# mcuboardschematic.net
KiCad netlist of a schematic drawn in EasyEDA Pro
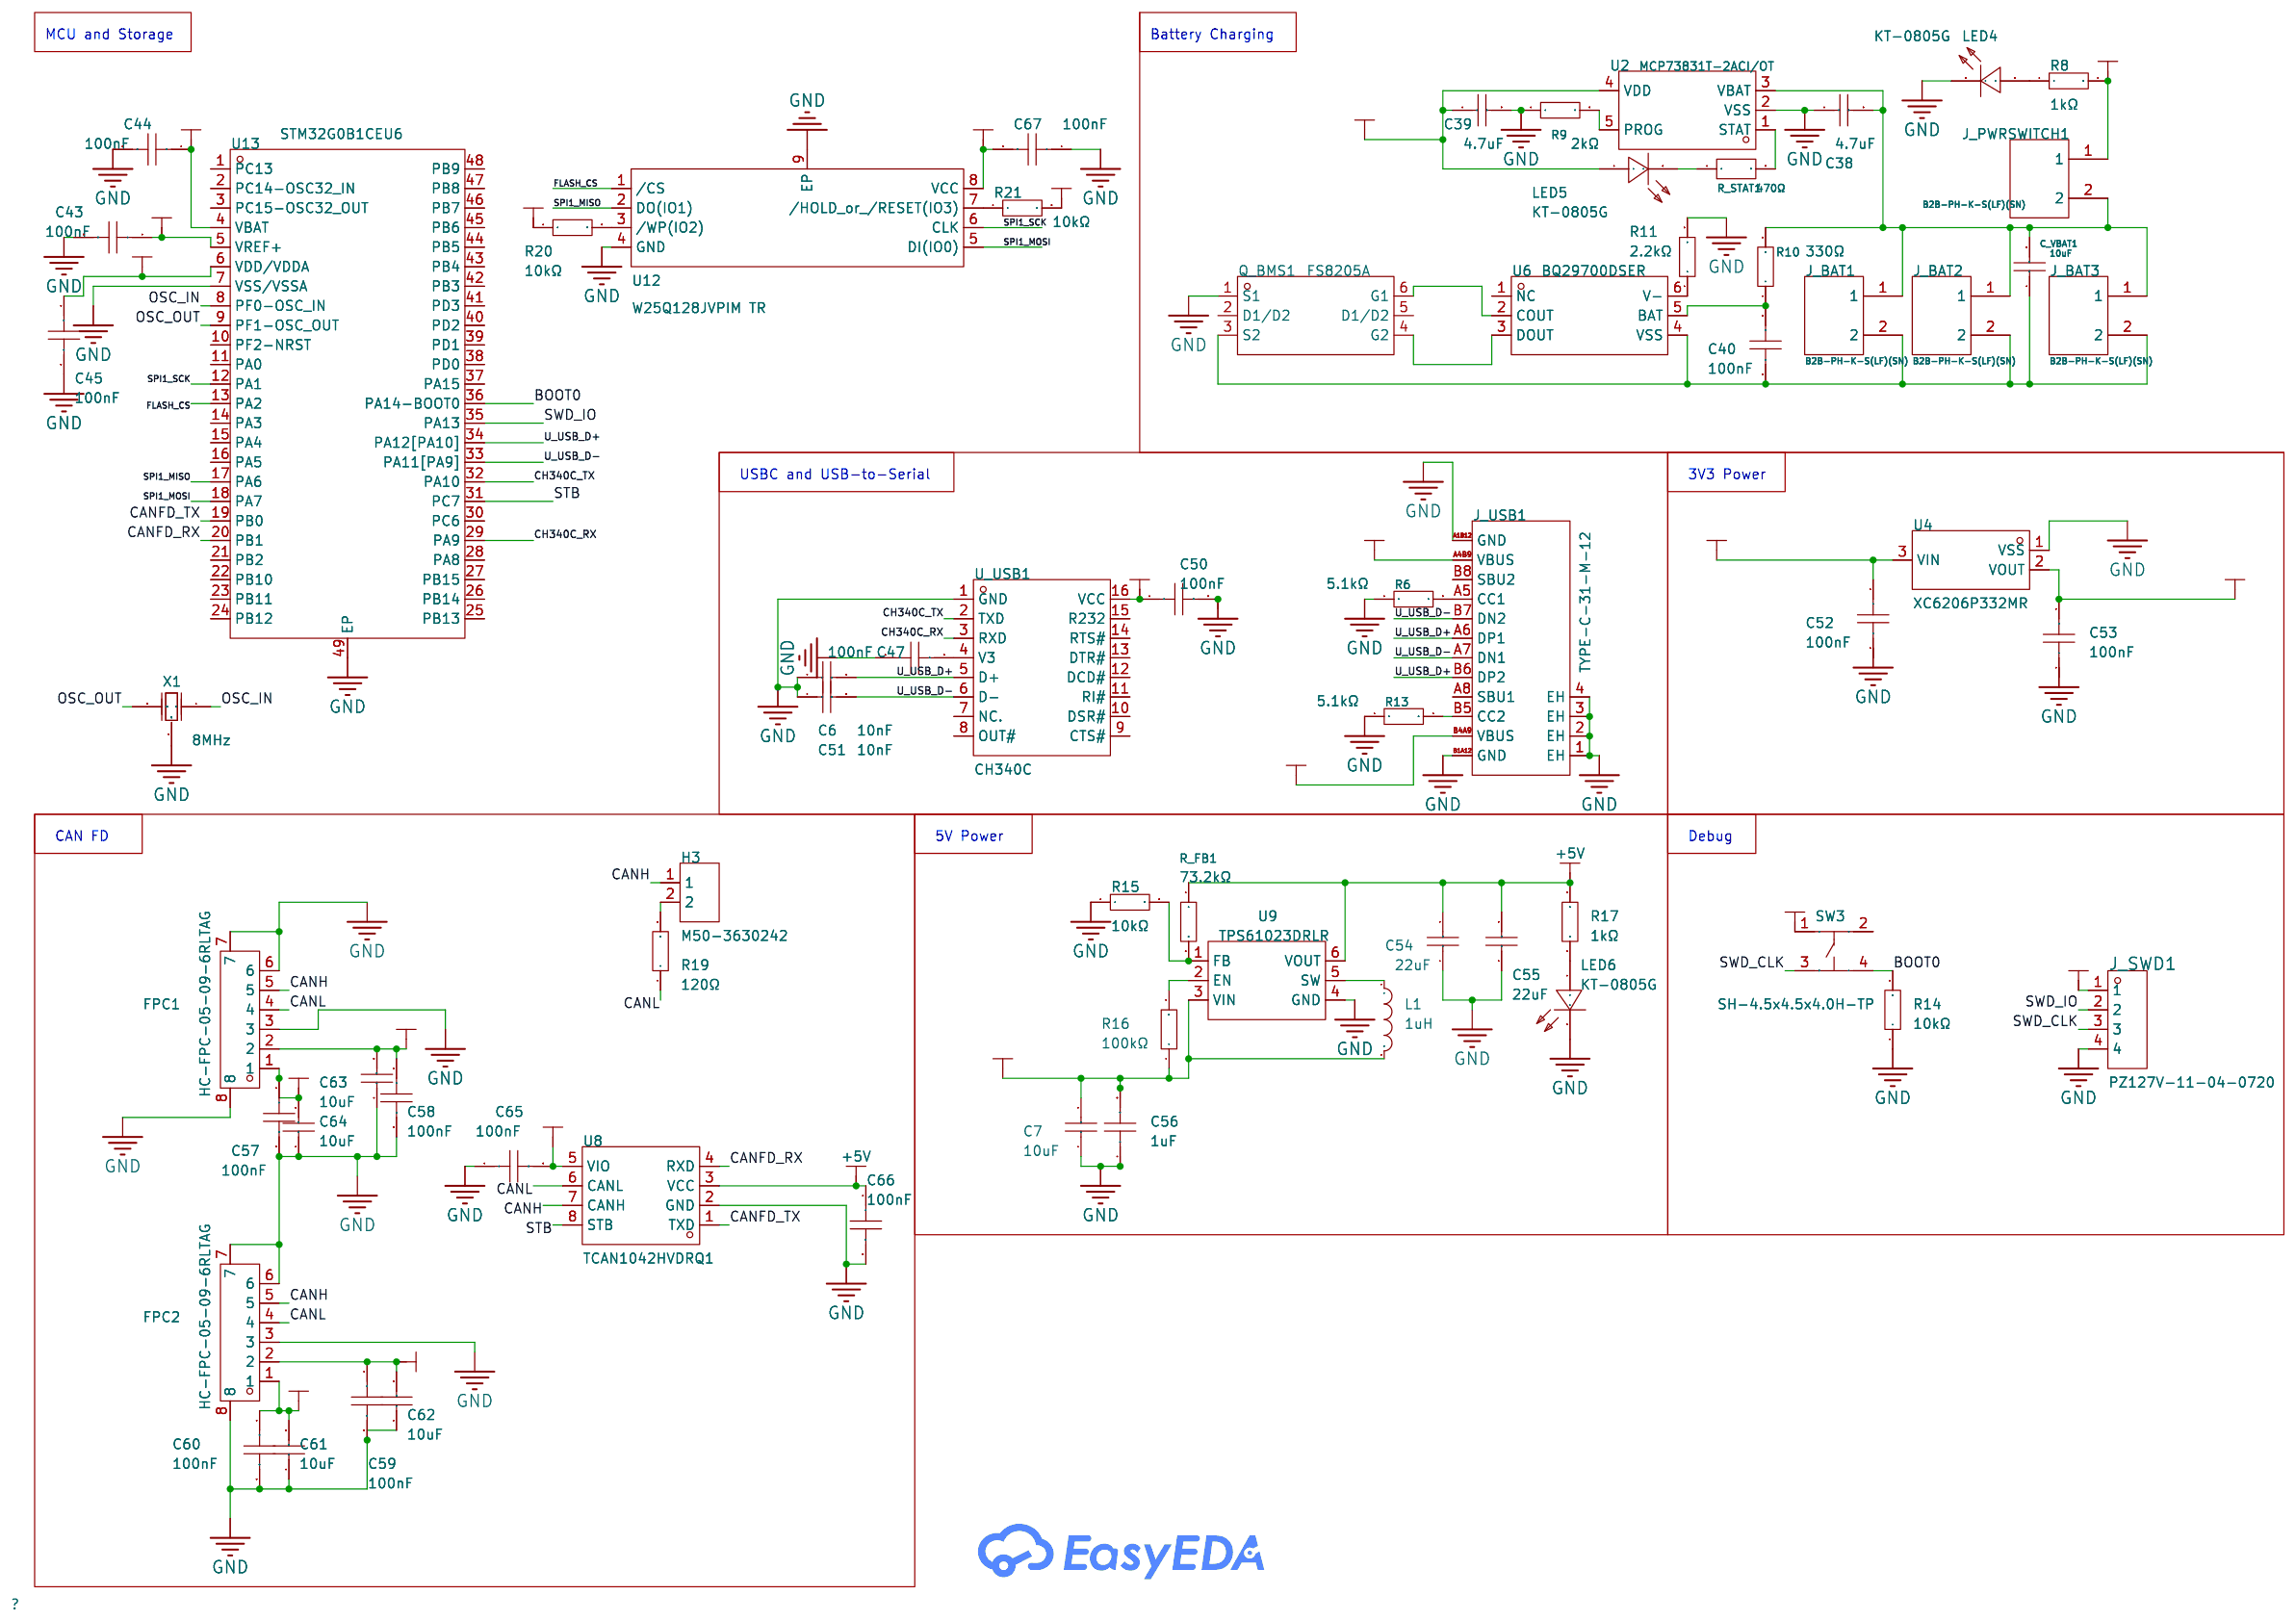
[diagram p0: schematic sheet]

(export (version "E")
  (design (tool "Eeschema 10.0.6"))
  (components
    (comp (ref "C6")
      (value "10nF")
      (footprint "easyedapro:C0402")
      (description "Capacitance:10nF Tolerance:±10% Tolerance:±10% Voltage Rating:50V Temperature Coefficient:X7R")
      (fields
        (field (name "Manufacturer Part") "CL05B103KB5NNNC")
        (field (name "Manufacturer") "SAMSUNG(三星)")
      )
      (libsource (lib "easyedapro") (part "CL05B103KB5NNNC"))
    )
    (comp (ref "C7")
      (value "10uF")
      (footprint "easyedapro:C0402")
      (description "Capacitance:10uF Tolerance:±20% Tolerance:±20% Voltage Rating:6.3V Temperature Coefficient:X5R")
      (fields
        (field (name "Manufacturer Part") "CL05A106MQ5NUNC")
        (field (name "Manufacturer") "SAMSUNG(三星)")
      )
      (libsource (lib "easyedapro") (part "CL05A106MQ5NUNC"))
    )
    (comp (ref "C38")
      (value "4.7uF")
      (footprint "easyedapro:C1206")
      (description "Capacitance:4.7uF Tolerance:±10% Tolerance:±10% Voltage Rating:25V Temperature Coefficient:X7R")
      (fields
        (field (name "Manufacturer Part") "CL31B475KAHNNNE")
        (field (name "Manufacturer") "SAMSUNG(三星)")
      )
      (libsource (lib "easyedapro") (part "CL31B475KAHNNNE"))
    )
    (comp (ref "C39")
      (value "4.7uF")
      (footprint "easyedapro:C1206")
      (description "Capacitance:4.7uF Tolerance:±10% Tolerance:±10% Voltage Rating:25V Temperature Coefficient:X7R")
      (fields
        (field (name "Manufacturer Part") "CL31B475KAHNNNE")
        (field (name "Manufacturer") "SAMSUNG(三星)")
      )
      (libsource (lib "easyedapro") (part "CL31B475KAHNNNE"))
    )
    (comp (ref "C40")
      (value "100nF")
      (footprint "easyedapro:C0402")
      (description "Capacitance:100nF Tolerance:±10% Tolerance:±10% Voltage Rating:16V Temperature Coefficient:X7R")
      (fields
        (field (name "Manufacturer Part") "CL05B104KO5NNNC")
        (field (name "Manufacturer") "SAMSUNG(三星)")
      )
      (libsource (lib "easyedapro") (part "CL05B104KO5NNNC"))
    )
    (comp (ref "C43")
      (value "100nF")
      (footprint "easyedapro:C0402")
      (description "Capacitance:100nF Tolerance:±10% Tolerance:±10% Voltage Rating:16V Temperature Coefficient:X7R")
      (fields
        (field (name "Manufacturer Part") "CL05B104KO5NNNC")
        (field (name "Manufacturer") "SAMSUNG(三星)")
      )
      (libsource (lib "easyedapro") (part "CL05B104KO5NNNC"))
    )
    (comp (ref "C44")
      (value "100nF")
      (footprint "easyedapro:C0402")
      (description "Capacitance:100nF Tolerance:±10% Tolerance:±10% Voltage Rating:16V Temperature Coefficient:X7R")
      (fields
        (field (name "Manufacturer Part") "CL05B104KO5NNNC")
        (field (name "Manufacturer") "SAMSUNG(三星)")
      )
      (libsource (lib "easyedapro") (part "CL05B104KO5NNNC"))
    )
    (comp (ref "C45")
      (value "100nF")
      (footprint "easyedapro:C0402")
      (description "Capacitance:100nF Tolerance:±10% Tolerance:±10% Voltage Rating:16V Temperature Coefficient:X7R")
      (fields
        (field (name "Manufacturer Part") "CL05B104KO5NNNC")
        (field (name "Manufacturer") "SAMSUNG(三星)")
      )
      (libsource (lib "easyedapro") (part "CL05B104KO5NNNC"))
    )
    (comp (ref "C47")
      (value "100nF")
      (footprint "easyedapro:C0402")
      (description "Capacitance:100nF Tolerance:±10% Tolerance:±10% Voltage Rating:16V Temperature Coefficient:X7R")
      (fields
        (field (name "Manufacturer Part") "CL05B104KO5NNNC")
        (field (name "Manufacturer") "SAMSUNG(三星)")
      )
      (libsource (lib "easyedapro") (part "CL05B104KO5NNNC"))
    )
    (comp (ref "C50")
      (value "100nF")
      (footprint "easyedapro:C0402")
      (description "Capacitance:100nF Tolerance:±10% Tolerance:±10% Voltage Rating:16V Temperature Coefficient:X7R")
      (fields
        (field (name "Manufacturer Part") "CL05B104KO5NNNC")
        (field (name "Manufacturer") "SAMSUNG(三星)")
      )
      (libsource (lib "easyedapro") (part "CL05B104KO5NNNC"))
    )
    (comp (ref "C51")
      (value "10nF")
      (footprint "easyedapro:C0402")
      (description "Capacitance:10nF Tolerance:±10% Tolerance:±10% Voltage Rating:50V Temperature Coefficient:X7R")
      (fields
        (field (name "Manufacturer Part") "CL05B103KB5NNNC")
        (field (name "Manufacturer") "SAMSUNG(三星)")
      )
      (libsource (lib "easyedapro") (part "CL05B103KB5NNNC"))
    )
    (comp (ref "C52")
      (value "100nF")
      (footprint "easyedapro:C0402")
      (description "Capacitance:100nF Tolerance:±10% Tolerance:±10% Voltage Rating:16V Temperature Coefficient:X7R")
      (fields
        (field (name "Manufacturer Part") "CL05B104KO5NNNC")
        (field (name "Manufacturer") "SAMSUNG(三星)")
      )
      (libsource (lib "easyedapro") (part "CL05B104KO5NNNC"))
    )
    (comp (ref "C53")
      (value "100nF")
      (footprint "easyedapro:C0402")
      (description "Capacitance:100nF Tolerance:±10% Tolerance:±10% Voltage Rating:16V Temperature Coefficient:X7R")
      (fields
        (field (name "Manufacturer Part") "CL05B104KO5NNNC")
        (field (name "Manufacturer") "SAMSUNG(三星)")
      )
      (libsource (lib "easyedapro") (part "CL05B104KO5NNNC"))
    )
    (comp (ref "C54")
      (value "22uF")
      (footprint "easyedapro:C1206")
      (description "Capacitance:22uF Tolerance:±10% Tolerance:±10% Voltage Rating:25V Temperature Coefficient:X5R")
      (fields
        (field (name "Manufacturer Part") "CL31A226KAHNNNE")
        (field (name "Manufacturer") "SAMSUNG(三星)")
      )
      (libsource (lib "easyedapro") (part "CL31A226KAHNNNE"))
    )
    (comp (ref "C55")
      (value "22uF")
      (footprint "easyedapro:C1206")
      (description "Capacitance:22uF Tolerance:±10% Tolerance:±10% Voltage Rating:25V Temperature Coefficient:X5R")
      (fields
        (field (name "Manufacturer Part") "CL31A226KAHNNNE")
        (field (name "Manufacturer") "SAMSUNG(三星)")
      )
      (libsource (lib "easyedapro") (part "CL31A226KAHNNNE"))
    )
    (comp (ref "C56")
      (value "1uF")
      (footprint "easyedapro:C0402")
      (description "Capacitance:1uF Tolerance:±10% Tolerance:±10% Voltage Rating:25V Temperature Coefficient:X5R")
      (fields
        (field (name "Manufacturer Part") "CL05A105KA5NQNC")
        (field (name "Manufacturer") "SAMSUNG(三星)")
      )
      (libsource (lib "easyedapro") (part "CL05A105KA5NQNC"))
    )
    (comp (ref "C57")
      (value "100nF")
      (footprint "easyedapro:C0402")
      (description "Capacitance:100nF Tolerance:±10% Tolerance:±10% Voltage Rating:16V Temperature Coefficient:X7R")
      (fields
        (field (name "Manufacturer Part") "CL05B104KO5NNNC")
        (field (name "Manufacturer") "SAMSUNG(三星)")
      )
      (libsource (lib "easyedapro") (part "CL05B104KO5NNNC"))
    )
    (comp (ref "C58")
      (value "100nF")
      (footprint "easyedapro:C0402")
      (description "Capacitance:100nF Tolerance:±10% Tolerance:±10% Voltage Rating:16V Temperature Coefficient:X7R")
      (fields
        (field (name "Manufacturer Part") "CL05B104KO5NNNC")
        (field (name "Manufacturer") "SAMSUNG(三星)")
      )
      (libsource (lib "easyedapro") (part "CL05B104KO5NNNC"))
    )
    (comp (ref "C59")
      (value "100nF")
      (footprint "easyedapro:C0402")
      (description "Capacitance:100nF Tolerance:±10% Tolerance:±10% Voltage Rating:16V Temperature Coefficient:X7R")
      (fields
        (field (name "Manufacturer Part") "CL05B104KO5NNNC")
        (field (name "Manufacturer") "SAMSUNG(三星)")
      )
      (libsource (lib "easyedapro") (part "CL05B104KO5NNNC"))
    )
    (comp (ref "C60")
      (value "100nF")
      (footprint "easyedapro:C0402")
      (description "Capacitance:100nF Tolerance:±10% Tolerance:±10% Voltage Rating:16V Temperature Coefficient:X7R")
      (fields
        (field (name "Manufacturer Part") "CL05B104KO5NNNC")
        (field (name "Manufacturer") "SAMSUNG(三星)")
      )
      (libsource (lib "easyedapro") (part "CL05B104KO5NNNC"))
    )
    (comp (ref "C61")
      (value "10uF")
      (footprint "easyedapro:C0402")
      (description "Capacitance:10uF Tolerance:±20% Tolerance:±20% Voltage Rating:6.3V Temperature Coefficient:X5R")
      (fields
        (field (name "Manufacturer Part") "CL05A106MQ5NUNC")
        (field (name "Manufacturer") "SAMSUNG(三星)")
      )
      (libsource (lib "easyedapro") (part "CL05A106MQ5NUNC"))
    )
    (comp (ref "C62")
      (value "10uF")
      (footprint "easyedapro:C0402")
      (description "Capacitance:10uF Tolerance:±20% Tolerance:±20% Voltage Rating:6.3V Temperature Coefficient:X5R")
      (fields
        (field (name "Manufacturer Part") "CL05A106MQ5NUNC")
        (field (name "Manufacturer") "SAMSUNG(三星)")
      )
      (libsource (lib "easyedapro") (part "CL05A106MQ5NUNC"))
    )
    (comp (ref "C63")
      (value "10uF")
      (footprint "easyedapro:C0402")
      (description "Capacitance:10uF Tolerance:±20% Tolerance:±20% Voltage Rating:6.3V Temperature Coefficient:X5R")
      (fields
        (field (name "Manufacturer Part") "CL05A106MQ5NUNC")
        (field (name "Manufacturer") "SAMSUNG(三星)")
      )
      (libsource (lib "easyedapro") (part "CL05A106MQ5NUNC"))
    )
    (comp (ref "C64")
      (value "10uF")
      (footprint "easyedapro:C0402")
      (description "Capacitance:10uF Tolerance:±20% Tolerance:±20% Voltage Rating:6.3V Temperature Coefficient:X5R")
      (fields
        (field (name "Manufacturer Part") "CL05A106MQ5NUNC")
        (field (name "Manufacturer") "SAMSUNG(三星)")
      )
      (libsource (lib "easyedapro") (part "CL05A106MQ5NUNC"))
    )
    (comp (ref "C65")
      (value "100nF")
      (footprint "easyedapro:C0402")
      (description "Capacitance:100nF Tolerance:±10% Tolerance:±10% Voltage Rating:16V Temperature Coefficient:X7R")
      (fields
        (field (name "Manufacturer Part") "CL05B104KO5NNNC")
        (field (name "Manufacturer") "SAMSUNG(三星)")
      )
      (libsource (lib "easyedapro") (part "CL05B104KO5NNNC"))
    )
    (comp (ref "C66")
      (value "100nF")
      (footprint "easyedapro:C0402")
      (description "Capacitance:100nF Tolerance:±10% Tolerance:±10% Voltage Rating:16V Temperature Coefficient:X7R")
      (fields
        (field (name "Manufacturer Part") "CL05B104KO5NNNC")
        (field (name "Manufacturer") "SAMSUNG(三星)")
      )
      (libsource (lib "easyedapro") (part "CL05B104KO5NNNC"))
    )
    (comp (ref "C67")
      (value "100nF")
      (footprint "easyedapro:C0402")
      (description "Capacitance:100nF Tolerance:±10% Tolerance:±10% Voltage Rating:16V Temperature Coefficient:X7R")
      (fields
        (field (name "Manufacturer Part") "CL05B104KO5NNNC")
        (field (name "Manufacturer") "SAMSUNG(三星)")
      )
      (libsource (lib "easyedapro") (part "CL05B104KO5NNNC"))
    )
    (comp (ref "C_VBAT1")
      (value "10uF")
      (footprint "easyedapro:C0402")
      (description "Capacitance:10uF Tolerance:±20% Tolerance:±20% Voltage Rating:6.3V Temperature Coefficient:X5R")
      (fields
        (field (name "Manufacturer Part") "CL05A106MQ5NUNC")
        (field (name "Manufacturer") "SAMSUNG(三星)")
      )
      (libsource (lib "easyedapro") (part "CL05A106MQ5NUNC"))
    )
    (comp (ref "FPC1")
      (value "HC-FPC-05-09-6RLTAG")
      (footprint "easyedapro:FPC-SMD_6P-P0.50_HC-FPC-05-09-6RLTAG")
      (fields (field (name "Manufacturer") "HCTL(华灿天禄)"))
      (libsource (lib "easyedapro") (part "HC-FPC-05-09-6RLTAG"))
    )
    (comp (ref "FPC2")
      (value "HC-FPC-05-09-6RLTAG")
      (footprint "easyedapro:FPC-SMD_6P-P0.50_HC-FPC-05-09-6RLTAG")
      (fields (field (name "Manufacturer") "HCTL(华灿天禄)"))
      (libsource (lib "easyedapro") (part "HC-FPC-05-09-6RLTAG"))
    )
    (comp (ref "H3")
      (value "M50-3630242")
      (footprint "easyedapro:HDR-SMD_2P-P1.27_M50-3630242")
      (fields (field (name "Manufacturer") "Harwin"))
      (libsource (lib "easyedapro") (part "M50-3630242"))
    )
    (comp (ref "J_BAT1")
      (value "B2B-PH-K-S(LF)(SN)")
      (footprint "easyedapro:CONN-TH_B2B-PH-K-S")
      (fields (field (name "Manufacturer") "JST"))
      (libsource (lib "easyedapro") (part "B2B-PH-K-S(LF)(SN)"))
    )
    (comp (ref "J_BAT2")
      (value "B2B-PH-K-S(LF)(SN)")
      (footprint "easyedapro:CONN-TH_B2B-PH-K-S")
      (fields (field (name "Manufacturer") "JST"))
      (libsource (lib "easyedapro") (part "B2B-PH-K-S(LF)(SN)"))
    )
    (comp (ref "J_BAT3")
      (value "B2B-PH-K-S(LF)(SN)")
      (footprint "easyedapro:CONN-TH_B2B-PH-K-S")
      (fields (field (name "Manufacturer") "JST"))
      (libsource (lib "easyedapro") (part "B2B-PH-K-S(LF)(SN)"))
    )
    (comp (ref "J_PWRSWITCH1")
      (value "B2B-PH-K-S(LF)(SN)")
      (footprint "easyedapro:CONN-TH_B2B-PH-K-S")
      (fields (field (name "Manufacturer") "JST"))
      (libsource (lib "easyedapro") (part "B2B-PH-K-S(LF)(SN)"))
    )
    (comp (ref "J_SWD1")
      (value "PZ127V-11-04-0720")
      (footprint "easyedapro:HDR-TH_4P-P1.27-V-M")
      (fields (field (name "Manufacturer") "XFCN(兴飞)"))
      (libsource (lib "easyedapro") (part "PZ127V-11-04-0720"))
    )
    (comp (ref "J_USB1")
      (value "TYPE-C-31-M-12")
      (footprint "easyedapro:USB-C_SMD-TYPE-C-31-M-12_1")
      (fields (field (name "Manufacturer") "韩国韩荣"))
      (libsource (lib "easyedapro") (part "TYPE-C-31-M-12"))
    )
    (comp (ref "L1")
      (value "1uH")
      (footprint "easyedapro:L0603")
      (fields (field (name "Manufacturer Part") "YL160808-1R0K") (field (name "Manufacturer") "YJYCOIN(益嘉源)"))
      (libsource (lib "easyedapro") (part "YL160808-1R0K"))
    )
    (comp (ref "LED4")
      (value "KT-0805G")
      (footprint "easyedapro:LED0805-R-RD")
      (fields (field (name "Manufacturer") "KENTO"))
      (libsource (lib "easyedapro") (part "0805G (Green)"))
    )
    (comp (ref "LED5")
      (value "KT-0805G")
      (footprint "easyedapro:LED0805-R-RD")
      (fields (field (name "Manufacturer") "KENTO"))
      (libsource (lib "easyedapro") (part "0805G (Green)"))
    )
    (comp (ref "LED6")
      (value "KT-0805G")
      (footprint "easyedapro:LED0805-R-RD")
      (fields (field (name "Manufacturer") "KENTO"))
      (libsource (lib "easyedapro") (part "0805G (Green)"))
    )
    (comp (ref "Q_BMS1")
      (value "FS8205A")
      (footprint "easyedapro:SOT-23-6_L2.9-W1.6-P0.95-LS2.8-BR")
      (fields (field (name "Manufacturer") "TECH PUBLIC(台舟)"))
      (libsource (lib "easyedapro") (part "FS8205A_C2830320"))
    )
    (comp (ref "R6")
      (value "5.1kΩ")
      (footprint "easyedapro:R0402")
      (fields
        (field (name "Manufacturer Part") "0402WGF5101TCE")
        (field (name "Manufacturer") "UNI-ROYAL(厚声)")
      )
      (libsource (lib "easyedapro") (part "0402WGF5101TCE"))
    )
    (comp (ref "R8")
      (value "1kΩ")
      (footprint "easyedapro:R0402")
      (fields
        (field (name "Manufacturer Part") "0402WGF1001TCE")
        (field (name "Manufacturer") "UNI-ROYAL(厚声)")
      )
      (libsource (lib "easyedapro") (part "0402WGF1001TCE"))
    )
    (comp (ref "R9")
      (value "2kΩ")
      (footprint "easyedapro:R0402")
      (fields
        (field (name "Manufacturer Part") "0402WGF2001TCE")
        (field (name "Manufacturer") "UNI-ROYAL(厚声)")
      )
      (libsource (lib "easyedapro") (part "0402WGF2001TCE"))
    )
    (comp (ref "R10")
      (value "330Ω")
      (footprint "easyedapro:R0805")
      (fields
        (field (name "Manufacturer Part") "0805W8F3300T5E")
        (field (name "Manufacturer") "UNI-ROYAL(厚声)")
      )
      (libsource (lib "easyedapro") (part "0805W8F3300T5E"))
    )
    (comp (ref "R11")
      (value "2.2kΩ")
      (footprint "easyedapro:R0805")
      (fields
        (field (name "Manufacturer Part") "0805W8F2201T5E")
        (field (name "Manufacturer") "UNI-ROYAL(厚声)")
      )
      (libsource (lib "easyedapro") (part "0805W8F2201T5E"))
    )
    (comp (ref "R13")
      (value "5.1kΩ")
      (footprint "easyedapro:R0402")
      (fields
        (field (name "Manufacturer Part") "0402WGF5101TCE")
        (field (name "Manufacturer") "UNI-ROYAL(厚声)")
      )
      (libsource (lib "easyedapro") (part "0402WGF5101TCE"))
    )
    (comp (ref "R14")
      (value "10kΩ")
      (footprint "easyedapro:R0402")
      (fields
        (field (name "Manufacturer Part") "0402WGF1002TCE")
        (field (name "Manufacturer") "UNI-ROYAL(厚声)")
      )
      (libsource (lib "easyedapro") (part "0402WGF1002TCE"))
    )
    (comp (ref "R15")
      (value "10kΩ")
      (footprint "easyedapro:R0402")
      (fields
        (field (name "Manufacturer Part") "0402WGF1002TCE")
        (field (name "Manufacturer") "UNI-ROYAL(厚声)")
      )
      (libsource (lib "easyedapro") (part "0402WGF1002TCE"))
    )
    (comp (ref "R16")
      (value "100kΩ")
      (footprint "easyedapro:R1206")
      (fields
        (field (name "Manufacturer Part") "1206W4F1003T5E")
        (field (name "Manufacturer") "UNI-ROYAL(厚声)")
      )
      (libsource (lib "easyedapro") (part "1206W4F1003T5E"))
    )
    (comp (ref "R17")
      (value "1kΩ")
      (footprint "easyedapro:R0402")
      (fields
        (field (name "Manufacturer Part") "0402WGF1001TCE")
        (field (name "Manufacturer") "UNI-ROYAL(厚声)")
      )
      (libsource (lib "easyedapro") (part "0402WGF1001TCE"))
    )
    (comp (ref "R19")
      (value "120Ω")
      (footprint "easyedapro:R0402")
      (fields
        (field (name "Manufacturer Part") "0402WGF1200TCE")
        (field (name "Manufacturer") "UNI-ROYAL(厚声)")
      )
      (libsource (lib "easyedapro") (part "0402WGF1200TCE"))
    )
    (comp (ref "R20")
      (value "10kΩ")
      (footprint "easyedapro:R0402")
      (fields
        (field (name "Manufacturer Part") "0402WGF1002TCE")
        (field (name "Manufacturer") "UNI-ROYAL(厚声)")
      )
      (libsource (lib "easyedapro") (part "0402WGF1002TCE"))
    )
    (comp (ref "R21")
      (value "10kΩ")
      (footprint "easyedapro:R0402")
      (fields
        (field (name "Manufacturer Part") "0402WGF1002TCE")
        (field (name "Manufacturer") "UNI-ROYAL(厚声)")
      )
      (libsource (lib "easyedapro") (part "0402WGF1002TCE"))
    )
    (comp (ref "R_FB1")
      (value "73.2kΩ")
      (footprint "easyedapro:R0402")
      (fields
        (field (name "Manufacturer Part") "0402WGF7322TCE")
        (field (name "Manufacturer") "UNI-ROYAL(厚声)")
      )
      (libsource (lib "easyedapro") (part "0402WGF7322TCE"))
    )
    (comp (ref "R_STAT1")
      (value "470Ω")
      (footprint "easyedapro:R0402")
      (fields (field (name "Manufacturer Part") "FRC0402F4700TS") (field (name "Manufacturer") "FOJAN(富捷)"))
      (libsource (lib "easyedapro") (part "FRC0402F4700TS"))
    )
    (comp (ref "SW3")
      (value "SH-4.5x4.5x4.0H-TP")
      (footprint "easyedapro:SW-SMD_4P-SH-4.5X4.5X4.0H-TP")
      (fields (field (name "Manufacturer") "SHOU HAN(首韩)"))
      (libsource (lib "easyedapro") (part "SH-4.5X4.5X4.0H-TP"))
    )
    (comp (ref "U2")
      (value "MCP73831T-2ACI/OT")
      (footprint "easyedapro:SOT-23-5_L3.0-W1.7-P0.95-LS2.8-BL")
      (fields (field (name "Manufacturer") "MICROCHIP(美国微芯)"))
      (libsource (lib "easyedapro") (part "MCP73831T-2ACI/OT"))
    )
    (comp (ref "U4")
      (value "XC6206P332MR")
      (footprint "easyedapro:SOT-23-3_L3.0-W1.7-P0.95-LS2.9-BR")
      (fields (field (name "Manufacturer") "UMW(友台半导体)"))
      (libsource (lib "easyedapro") (part "XC6206P332MR_C347376"))
    )
    (comp (ref "U6")
      (value "BQ29700DSER")
      (footprint "easyedapro:WSON-6_L1.5-W1.5-P0.50-TL")
      (fields (field (name "Manufacturer") "TI(德州仪器)"))
      (libsource (lib "easyedapro") (part "BQ29700DSER"))
    )
    (comp (ref "U8")
      (value "TCAN1042HVDRQ1")
      (footprint "easyedapro:SOIC-8_L4.9-W3.9-P1.27-LS6.0-BL")
      (fields (field (name "Manufacturer") "TI(德州仪器)"))
      (libsource (lib "easyedapro") (part "TCAN1042HVDRQ1"))
    )
    (comp (ref "U9")
      (value "TPS61023DRLR")
      (footprint "easyedapro:SOT-563_L1.6-W1.2-P0.50-LS1.6-BR")
      (fields (field (name "Manufacturer") "TI(德州仪器)"))
      (libsource (lib "easyedapro") (part "TPS61023DRLR"))
    )
    (comp (ref "U12")
      (value "W25Q128JVPIM TR")
      (footprint "easyedapro:WSON-8_L6.0-W5.0-P1.27-BL-EP")
      (fields (field (name "Manufacturer") "Winbond(华邦)"))
      (libsource (lib "easyedapro") (part "W25Q128JVPIM TR"))
    )
    (comp (ref "U13")
      (value "STM32G0B1CEU6")
      (footprint "easyedapro:UFQFPN-48_L7.0-W7.0-P0.50-BL-EP")
      (fields (field (name "Manufacturer") "ST(意法半导体)"))
      (libsource (lib "easyedapro") (part "STM32G0B1CEU6"))
    )
    (comp (ref "U_USB1")
      (value "CH340C")
      (footprint "easyedapro:SOP-16_L10.0-W3.9-P1.27-LS6.0-BL")
      (fields (field (name "Manufacturer") "WCH(南京沁恒)"))
      (libsource (lib "easyedapro") (part "CH340C"))
    )
    (comp (ref "X1")
      (value "8MHz")
      (footprint "easyedapro:OSC-SMD_3P-L3.2-W1.3-P1.20-L")
      (fields
        (field (name "Manufacturer Part") "CSTNE8M00GH5C000R0")
        (field (name "Manufacturer") "muRata(村田)")
      )
      (libsource (lib "easyedapro") (part "CSTNE8M00GH5C000R0"))
    )
  )
  (nets
    (net (code "1") (name "+5V") (class "Default")
      (node (ref "C54") (pin "2") (pinfunction "2_2") (pintype "input"))
      (node (ref "C55") (pin "2") (pinfunction "2_2") (pintype "input"))
      (node (ref "C66") (pin "1") (pinfunction "1_1") (pintype "unspecified"))
      (node (ref "R17") (pin "2") (pinfunction "2_2") (pintype "input"))
      (node (ref "R_FB1") (pin "1") (pinfunction "1_1") (pintype "input"))
      (node (ref "U8") (pin "3") (pinfunction "VCC_3") (pintype "unspecified"))
      (node (ref "U9") (pin "6") (pinfunction "VOUT_6") (pintype "unspecified"))
    )
    (net (code "2") (name "/BOOT0") (class "Default")
      (node (ref "R14") (pin "2") (pinfunction "2_2") (pintype "input"))
      (node (ref "SW3") (pin "4") (pinfunction "4_4") (pintype "unspecified"))
      (node (ref "U13") (pin "36") (pinfunction "PA14-BOOT0_36") (pintype "unspecified"))
    )
    (net (code "3") (name "/CANFD_RX") (class "Default")
      (node (ref "U13") (pin "20") (pinfunction "PB1_20") (pintype "unspecified"))
      (node (ref "U8") (pin "4") (pinfunction "RXD_4") (pintype "unspecified"))
    )
    (net (code "4") (name "/CANFD_TX") (class "Default")
      (node (ref "U13") (pin "19") (pinfunction "PB0_19") (pintype "unspecified"))
      (node (ref "U8") (pin "1") (pinfunction "TXD_1") (pintype "unspecified"))
    )
    (net (code "5") (name "/CANH") (class "Default")
      (node (ref "FPC1") (pin "5") (pinfunction "5_5") (pintype "unspecified"))
      (node (ref "FPC2") (pin "5") (pinfunction "5_5") (pintype "unspecified"))
      (node (ref "H3") (pin "1") (pinfunction "1_1") (pintype "unspecified"))
      (node (ref "U8") (pin "7") (pinfunction "CANH_7") (pintype "unspecified"))
    )
    (net (code "6") (name "/CANL") (class "Default")
      (node (ref "FPC1") (pin "4") (pinfunction "4_4") (pintype "unspecified"))
      (node (ref "FPC2") (pin "4") (pinfunction "4_4") (pintype "unspecified"))
      (node (ref "R19") (pin "1") (pinfunction "1_1") (pintype "input"))
      (node (ref "U8") (pin "6") (pinfunction "CANL_6") (pintype "unspecified"))
    )
    (net (code "7") (name "/CH340C_RX") (class "Default")
      (node (ref "U13") (pin "29") (pinfunction "PA9_29") (pintype "unspecified"))
      (node (ref "U_USB1") (pin "3") (pinfunction "RXD_3") (pintype "unspecified"))
    )
    (net (code "8") (name "/CH340C_TX") (class "Default")
      (node (ref "U13") (pin "32") (pinfunction "PA10_32") (pintype "unspecified"))
      (node (ref "U_USB1") (pin "2") (pinfunction "TXD_2") (pintype "unspecified"))
    )
    (net (code "9") (name "/FLASH_CS") (class "Default")
      (node (ref "U12") (pin "1") (pinfunction "/CS_1") (pintype "unspecified"))
      (node (ref "U13") (pin "13") (pinfunction "PA2_13") (pintype "unspecified"))
    )
    (net (code "10") (name "/OSC_IN") (class "Default")
      (node (ref "U13") (pin "8") (pinfunction "PF0-OSC_IN_8") (pintype "unspecified"))
      (node (ref "X1") (pin "1") (pinfunction "OSC1_1") (pintype "input"))
    )
    (net (code "11") (name "/OSC_OUT") (class "Default")
      (node (ref "U13") (pin "9") (pinfunction "PF1-OSC_OUT_9") (pintype "unspecified"))
      (node (ref "X1") (pin "3") (pinfunction "OSC2_3") (pintype "input"))
    )
    (net (code "12") (name "/SPI1_MISO") (class "Default")
      (node (ref "U12") (pin "2") (pinfunction "DO(IO1)_2") (pintype "unspecified"))
      (node (ref "U13") (pin "17") (pinfunction "PA6_17") (pintype "unspecified"))
    )
    (net (code "13") (name "/SPI1_MOSI") (class "Default")
      (node (ref "U12") (pin "5") (pinfunction "DI(IO0)_5") (pintype "unspecified"))
      (node (ref "U13") (pin "18") (pinfunction "PA7_18") (pintype "unspecified"))
    )
    (net (code "14") (name "/SPI1_SCK") (class "Default")
      (node (ref "U12") (pin "6") (pinfunction "CLK_6") (pintype "unspecified"))
      (node (ref "U13") (pin "12") (pinfunction "PA1_12") (pintype "unspecified"))
    )
    (net (code "15") (name "/STB") (class "Default")
      (node (ref "U13") (pin "31") (pinfunction "PC7_31") (pintype "unspecified"))
      (node (ref "U8") (pin "8") (pinfunction "STB_8") (pintype "unspecified"))
    )
    (net (code "16") (name "/SWD_CLK") (class "Default")
      (node (ref "J_SWD1") (pin "3") (pinfunction "3_3") (pintype "input"))
      (node (ref "SW3") (pin "3") (pinfunction "3_3") (pintype "unspecified"))
    )
    (net (code "17") (name "/SWD_IO") (class "Default")
      (node (ref "J_SWD1") (pin "2") (pinfunction "2_2") (pintype "input"))
      (node (ref "U13") (pin "35") (pinfunction "PA13_35") (pintype "unspecified"))
    )
    (net (code "18") (name "/U_USB_D+") (class "Default")
      (node (ref "C6") (pin "2") (pinfunction "2_2") (pintype "input"))
      (node (ref "J_USB1") (pin "A6") (pinfunction "DP1_A6") (pintype "unspecified"))
      (node (ref "J_USB1") (pin "B6") (pinfunction "DP2_B6") (pintype "unspecified"))
      (node (ref "U13") (pin "34") (pinfunction "PA12[PA10]_34") (pintype "unspecified"))
      (node (ref "U_USB1") (pin "5") (pinfunction "D+_5") (pintype "unspecified"))
    )
    (net (code "19") (name "/U_USB_D-") (class "Default")
      (node (ref "C51") (pin "2") (pinfunction "2_2") (pintype "input"))
      (node (ref "J_USB1") (pin "A7") (pinfunction "DN1_A7") (pintype "unspecified"))
      (node (ref "J_USB1") (pin "B7") (pinfunction "DN2_B7") (pintype "unspecified"))
      (node (ref "U13") (pin "33") (pinfunction "PA11[PA9]_33") (pintype "unspecified"))
      (node (ref "U_USB1") (pin "6") (pinfunction "D-_6") (pintype "unspecified"))
    )
    (net (code "20") (name "3V3") (class "Default")
      (node (ref "C43") (pin "1") (pinfunction "1_1") (pintype "unspecified"))
      (node (ref "C44") (pin "1") (pinfunction "1_1") (pintype "unspecified"))
      (node (ref "C45") (pin "1") (pinfunction "1_1") (pintype "unspecified"))
      (node (ref "C50") (pin "1") (pinfunction "1_1") (pintype "unspecified"))
      (node (ref "C53") (pin "2") (pinfunction "2_2") (pintype "unspecified"))
      (node (ref "C57") (pin "1") (pinfunction "1_1") (pintype "unspecified"))
      (node (ref "C60") (pin "1") (pinfunction "1_1") (pintype "unspecified"))
      (node (ref "C61") (pin "2") (pinfunction "2_2") (pintype "input"))
      (node (ref "C64") (pin "2") (pinfunction "2_2") (pintype "input"))
      (node (ref "C65") (pin "2") (pinfunction "2_2") (pintype "unspecified"))
      (node (ref "C67") (pin "2") (pinfunction "2_2") (pintype "unspecified"))
      (node (ref "FPC1") (pin "1") (pinfunction "1_1") (pintype "unspecified"))
      (node (ref "FPC2") (pin "1") (pinfunction "1_1") (pintype "unspecified"))
      (node (ref "J_SWD1") (pin "1") (pinfunction "1_1") (pintype "input"))
      (node (ref "R20") (pin "1") (pinfunction "1_1") (pintype "input"))
      (node (ref "R21") (pin "2") (pinfunction "2_2") (pintype "input"))
      (node (ref "SW3") (pin "1") (pinfunction "1_1") (pintype "unspecified"))
      (node (ref "U12") (pin "8") (pinfunction "VCC_8") (pintype "unspecified"))
      (node (ref "U13") (pin "4") (pinfunction "VBAT_4") (pintype "unspecified"))
      (node (ref "U13") (pin "5") (pinfunction "VREF+_5") (pintype "unspecified"))
      (node (ref "U13") (pin "6") (pinfunction "VDD/VDDA_6") (pintype "unspecified"))
      (node (ref "U4") (pin "2") (pinfunction "VOUT_2") (pintype "unspecified"))
      (node (ref "U8") (pin "5") (pinfunction "VIO_5") (pintype "unspecified"))
      (node (ref "U_USB1") (pin "16") (pinfunction "VCC_16") (pintype "unspecified"))
    )
    (net (code "21") (name "GND") (class "Default")
      (node (ref "C38") (pin "1") (pinfunction "1_1") (pintype "input"))
      (node (ref "C39") (pin "2") (pinfunction "2_2") (pintype "input"))
      (node (ref "C43") (pin "2") (pinfunction "2_2") (pintype "unspecified"))
      (node (ref "C44") (pin "2") (pinfunction "2_2") (pintype "unspecified"))
      (node (ref "C45") (pin "2") (pinfunction "2_2") (pintype "unspecified"))
      (node (ref "C47") (pin "1") (pinfunction "1_1") (pintype "unspecified"))
      (node (ref "C50") (pin "2") (pinfunction "2_2") (pintype "unspecified"))
      (node (ref "C51") (pin "1") (pinfunction "1_1") (pintype "input"))
      (node (ref "C52") (pin "1") (pinfunction "1_1") (pintype "unspecified"))
      (node (ref "C53") (pin "1") (pinfunction "1_1") (pintype "unspecified"))
      (node (ref "C54") (pin "1") (pinfunction "1_1") (pintype "input"))
      (node (ref "C55") (pin "1") (pinfunction "1_1") (pintype "input"))
      (node (ref "C56") (pin "1") (pinfunction "1_1") (pintype "unspecified"))
      (node (ref "C57") (pin "2") (pinfunction "2_2") (pintype "unspecified"))
      (node (ref "C58") (pin "2") (pinfunction "2_2") (pintype "unspecified"))
      (node (ref "C59") (pin "2") (pinfunction "2_2") (pintype "unspecified"))
      (node (ref "C6") (pin "1") (pinfunction "1_1") (pintype "input"))
      (node (ref "C60") (pin "2") (pinfunction "2_2") (pintype "unspecified"))
      (node (ref "C61") (pin "1") (pinfunction "1_1") (pintype "input"))
      (node (ref "C62") (pin "1") (pinfunction "1_1") (pintype "input"))
      (node (ref "C63") (pin "1") (pinfunction "1_1") (pintype "input"))
      (node (ref "C64") (pin "1") (pinfunction "1_1") (pintype "input"))
      (node (ref "C65") (pin "1") (pinfunction "1_1") (pintype "unspecified"))
      (node (ref "C66") (pin "2") (pinfunction "2_2") (pintype "unspecified"))
      (node (ref "C67") (pin "1") (pinfunction "1_1") (pintype "unspecified"))
      (node (ref "C7") (pin "1") (pinfunction "1_1") (pintype "input"))
      (node (ref "FPC1") (pin "3") (pinfunction "3_3") (pintype "unspecified"))
      (node (ref "FPC1") (pin "6") (pinfunction "6_6") (pintype "unspecified"))
      (node (ref "FPC1") (pin "7") (pinfunction "7_7") (pintype "unspecified"))
      (node (ref "FPC1") (pin "8") (pinfunction "8_8") (pintype "unspecified"))
      (node (ref "FPC2") (pin "3") (pinfunction "3_3") (pintype "unspecified"))
      (node (ref "FPC2") (pin "6") (pinfunction "6_6") (pintype "unspecified"))
      (node (ref "FPC2") (pin "7") (pinfunction "7_7") (pintype "unspecified"))
      (node (ref "FPC2") (pin "8") (pinfunction "8_8") (pintype "unspecified"))
      (node (ref "J_SWD1") (pin "4") (pinfunction "4_4") (pintype "input"))
      (node (ref "J_USB1") (pin "1") (pinfunction "EH_1") (pintype "unspecified"))
      (node (ref "J_USB1") (pin "2") (pinfunction "EH_2") (pintype "unspecified"))
      (node (ref "J_USB1") (pin "3") (pinfunction "EH_3") (pintype "unspecified"))
      (node (ref "J_USB1") (pin "4") (pinfunction "EH_4") (pintype "unspecified"))
      (node (ref "J_USB1") (pin "A1B12") (pinfunction "GND_A1B12") (pintype "unspecified"))
      (node (ref "J_USB1") (pin "B1A12") (pinfunction "GND_B1A12") (pintype "unspecified"))
      (node (ref "LED4") (pin "2") (pinfunction "K_2") (pintype "unspecified"))
      (node (ref "LED6") (pin "2") (pinfunction "K_2") (pintype "unspecified"))
      (node (ref "Q_BMS1") (pin "1") (pinfunction "S1_1") (pintype "unspecified"))
      (node (ref "R11") (pin "2") (pinfunction "2_2") (pintype "input"))
      (node (ref "R13") (pin "1") (pinfunction "1_1") (pintype "input"))
      (node (ref "R14") (pin "1") (pinfunction "1_1") (pintype "input"))
      (node (ref "R15") (pin "1") (pinfunction "1_1") (pintype "input"))
      (node (ref "R6") (pin "1") (pinfunction "1_1") (pintype "input"))
      (node (ref "R9") (pin "1") (pinfunction "1_1") (pintype "input"))
      (node (ref "U12") (pin "4") (pinfunction "GND_4") (pintype "unspecified"))
      (node (ref "U12") (pin "9") (pinfunction "EP_9") (pintype "unspecified"))
      (node (ref "U13") (pin "49") (pinfunction "EP_49") (pintype "unspecified"))
      (node (ref "U13") (pin "7") (pinfunction "VSS/VSSA_7") (pintype "unspecified"))
      (node (ref "U2") (pin "2") (pinfunction "VSS_2") (pintype "unspecified"))
      (node (ref "U4") (pin "1") (pinfunction "VSS_1") (pintype "unspecified"))
      (node (ref "U8") (pin "2") (pinfunction "GND_2") (pintype "unspecified"))
      (node (ref "U9") (pin "4") (pinfunction "GND_4") (pintype "unspecified"))
      (node (ref "U_USB1") (pin "1") (pinfunction "GND_1") (pintype "unspecified"))
      (node (ref "X1") (pin "2") (pinfunction "GND_2") (pintype "input"))
    )
    (net (code "22") (name "Net-(H3-Pad2)") (class "Default")
      (node (ref "H3") (pin "2") (pinfunction "2_2") (pintype "unspecified"))
      (node (ref "R19") (pin "2") (pinfunction "2_2") (pintype "input"))
    )
    (net (code "23") (name "Net-(J_USB1-CC1)") (class "Default")
      (node (ref "J_USB1") (pin "A5") (pinfunction "CC1_A5") (pintype "unspecified"))
      (node (ref "R6") (pin "2") (pinfunction "2_2") (pintype "input"))
    )
    (net (code "24") (name "Net-(J_USB1-CC2)") (class "Default")
      (node (ref "J_USB1") (pin "B5") (pinfunction "CC2_B5") (pintype "unspecified"))
      (node (ref "R13") (pin "2") (pinfunction "2_2") (pintype "input"))
    )
    (net (code "25") (name "Net-(LED4-A)") (class "Default")
      (node (ref "LED4") (pin "1") (pinfunction "A_1") (pintype "unspecified"))
      (node (ref "R8") (pin "1") (pinfunction "1_1") (pintype "input"))
    )
    (net (code "26") (name "Net-(LED5-K)") (class "Default")
      (node (ref "LED5") (pin "2") (pinfunction "K_2") (pintype "unspecified"))
      (node (ref "R_STAT1") (pin "1") (pinfunction "1_1") (pintype "unspecified"))
    )
    (net (code "27") (name "Net-(LED6-A)") (class "Default")
      (node (ref "LED6") (pin "1") (pinfunction "A_1") (pintype "unspecified"))
      (node (ref "R17") (pin "1") (pinfunction "1_1") (pintype "input"))
    )
    (net (code "28") (name "Net-(Q_BMS1-G1)") (class "Default")
      (node (ref "Q_BMS1") (pin "6") (pinfunction "G1_6") (pintype "unspecified"))
      (node (ref "U6") (pin "2") (pinfunction "COUT_2") (pintype "input"))
    )
    (net (code "29") (name "Net-(Q_BMS1-G2)") (class "Default")
      (node (ref "Q_BMS1") (pin "4") (pinfunction "G2_4") (pintype "unspecified"))
      (node (ref "U6") (pin "3") (pinfunction "DOUT_3") (pintype "input"))
    )
    (net (code "30") (name "Net-(Q_BMS1-S2)") (class "Default")
      (node (ref "C40") (pin "1") (pinfunction "1_1") (pintype "unspecified"))
      (node (ref "C_VBAT1") (pin "1") (pinfunction "1_1") (pintype "input"))
      (node (ref "J_BAT1") (pin "2") (pinfunction "2_2") (pintype "input"))
      (node (ref "J_BAT2") (pin "2") (pinfunction "2_2") (pintype "input"))
      (node (ref "J_BAT3") (pin "2") (pinfunction "2_2") (pintype "input"))
      (node (ref "Q_BMS1") (pin "3") (pinfunction "S2_3") (pintype "unspecified"))
      (node (ref "U6") (pin "4") (pinfunction "VSS_4") (pintype "input"))
    )
    (net (code "31") (name "Net-(U2-PROG)") (class "Default")
      (node (ref "R9") (pin "2") (pinfunction "2_2") (pintype "input"))
      (node (ref "U2") (pin "5") (pinfunction "PROG_5") (pintype "unspecified"))
    )
    (net (code "32") (name "Net-(U2-STAT)") (class "Default")
      (node (ref "R_STAT1") (pin "2") (pinfunction "2_2") (pintype "unspecified"))
      (node (ref "U2") (pin "1") (pinfunction "STAT_1") (pintype "unspecified"))
    )
    (net (code "33") (name "Net-(U2-VBAT)") (class "Default")
      (node (ref "C38") (pin "2") (pinfunction "2_2") (pintype "input"))
      (node (ref "C_VBAT1") (pin "2") (pinfunction "2_2") (pintype "input"))
      (node (ref "J_BAT1") (pin "1") (pinfunction "1_1") (pintype "input"))
      (node (ref "J_BAT2") (pin "1") (pinfunction "1_1") (pintype "input"))
      (node (ref "J_BAT3") (pin "1") (pinfunction "1_1") (pintype "input"))
      (node (ref "J_PWRSWITCH1") (pin "2") (pinfunction "2_2") (pintype "input"))
      (node (ref "R10") (pin "2") (pinfunction "2_2") (pintype "input"))
      (node (ref "U2") (pin "3") (pinfunction "VBAT_3") (pintype "unspecified"))
    )
    (net (code "34") (name "Net-(U6-BAT)") (class "Default")
      (node (ref "C40") (pin "2") (pinfunction "2_2") (pintype "unspecified"))
      (node (ref "R10") (pin "1") (pinfunction "1_1") (pintype "input"))
      (node (ref "U6") (pin "5") (pinfunction "BAT_5") (pintype "input"))
    )
    (net (code "35") (name "Net-(U6-V-)") (class "Default")
      (node (ref "R11") (pin "1") (pinfunction "1_1") (pintype "input"))
      (node (ref "U6") (pin "6") (pinfunction "V-_6") (pintype "input"))
    )
    (net (code "36") (name "Net-(U9-EN)") (class "Default")
      (node (ref "R16") (pin "2") (pinfunction "2_2") (pintype "input"))
      (node (ref "U9") (pin "2") (pinfunction "EN_2") (pintype "unspecified"))
    )
    (net (code "37") (name "Net-(U9-FB)") (class "Default")
      (node (ref "R15") (pin "2") (pinfunction "2_2") (pintype "input"))
      (node (ref "R_FB1") (pin "2") (pinfunction "2_2") (pintype "input"))
      (node (ref "U9") (pin "1") (pinfunction "FB_1") (pintype "unspecified"))
    )
    (net (code "38") (name "Net-(U9-SW)") (class "Default")
      (node (ref "L1") (pin "1") (pinfunction "1_1") (pintype "unspecified"))
      (node (ref "U9") (pin "5") (pinfunction "SW_5") (pintype "unspecified"))
    )
    (net (code "39") (name "Net-(U12-{slash}HOLD_or_{slash}RESET(IO3))") (class "Default")
      (node (ref "R21") (pin "1") (pinfunction "1_1") (pintype "input"))
      (node (ref "U12") (pin "7") (pinfunction "/HOLD_or_/RESET(IO3)_7") (pintype "unspecified"))
    )
    (net (code "40") (name "Net-(U12-{slash}WP(IO2))") (class "Default")
      (node (ref "R20") (pin "2") (pinfunction "2_2") (pintype "input"))
      (node (ref "U12") (pin "3") (pinfunction "/WP(IO2)_3") (pintype "unspecified"))
    )
    (net (code "41") (name "Net-(U_USB1-V3)") (class "Default")
      (node (ref "C47") (pin "2") (pinfunction "2_2") (pintype "unspecified"))
      (node (ref "U_USB1") (pin "4") (pinfunction "V3_4") (pintype "unspecified"))
    )
    (net (code "42") (name "VBAT") (class "Default")
      (node (ref "C52") (pin "2") (pinfunction "2_2") (pintype "unspecified"))
      (node (ref "C56") (pin "2") (pinfunction "2_2") (pintype "unspecified"))
      (node (ref "C58") (pin "1") (pinfunction "1_1") (pintype "unspecified"))
      (node (ref "C59") (pin "1") (pinfunction "1_1") (pintype "unspecified"))
      (node (ref "C62") (pin "2") (pinfunction "2_2") (pintype "input"))
      (node (ref "C63") (pin "2") (pinfunction "2_2") (pintype "input"))
      (node (ref "C7") (pin "2") (pinfunction "2_2") (pintype "input"))
      (node (ref "FPC1") (pin "2") (pinfunction "2_2") (pintype "unspecified"))
      (node (ref "FPC2") (pin "2") (pinfunction "2_2") (pintype "unspecified"))
      (node (ref "J_PWRSWITCH1") (pin "1") (pinfunction "1_1") (pintype "input"))
      (node (ref "L1") (pin "2") (pinfunction "2_2") (pintype "unspecified"))
      (node (ref "R16") (pin "1") (pinfunction "1_1") (pintype "input"))
      (node (ref "R8") (pin "2") (pinfunction "2_2") (pintype "input"))
      (node (ref "U4") (pin "3") (pinfunction "VIN_3") (pintype "unspecified"))
      (node (ref "U9") (pin "3") (pinfunction "VIN_3") (pintype "unspecified"))
    )
    (net (code "43") (name "VBUS_5V") (class "Default")
      (node (ref "C39") (pin "1") (pinfunction "1_1") (pintype "input"))
      (node (ref "J_USB1") (pin "A4B9") (pinfunction "VBUS_A4B9") (pintype "unspecified"))
      (node (ref "J_USB1") (pin "B4A9") (pinfunction "VBUS_B4A9") (pintype "unspecified"))
      (node (ref "LED5") (pin "1") (pinfunction "A_1") (pintype "unspecified"))
      (node (ref "U2") (pin "4") (pinfunction "VDD_4") (pintype "unspecified"))
    )
    (net (code "44") (name "unconnected-(J_USB1-SBU1-PadA8)") (class "Default")
      (node (ref "J_USB1") (pin "A8") (pinfunction "SBU1_A8") (pintype "unspecified"))
    )
    (net (code "45") (name "unconnected-(J_USB1-SBU2-PadB8)") (class "Default")
      (node (ref "J_USB1") (pin "B8") (pinfunction "SBU2_B8") (pintype "unspecified"))
    )
    (net (code "46") (name "unconnected-(Q_BMS1-D1{slash}D2-Pad2)") (class "Default")
      (node (ref "Q_BMS1") (pin "2") (pinfunction "D1/D2_2") (pintype "unspecified"))
    )
    (net (code "47") (name "unconnected-(Q_BMS1-D1{slash}D2-Pad5)") (class "Default")
      (node (ref "Q_BMS1") (pin "5") (pinfunction "D1/D2_5") (pintype "unspecified"))
    )
    (net (code "48") (name "unconnected-(SW3-Pad2)") (class "Default")
      (node (ref "SW3") (pin "2") (pinfunction "2_2") (pintype "unspecified"))
    )
    (net (code "49") (name "unconnected-(U6-NC-Pad1)") (class "Default")
      (node (ref "U6") (pin "1") (pinfunction "NC_1") (pintype "input"))
    )
    (net (code "50") (name "unconnected-(U13-PA0-Pad11)") (class "Default")
      (node (ref "U13") (pin "11") (pinfunction "PA0_11") (pintype "unspecified"))
    )
    (net (code "51") (name "unconnected-(U13-PA3-Pad14)") (class "Default")
      (node (ref "U13") (pin "14") (pinfunction "PA3_14") (pintype "unspecified"))
    )
    (net (code "52") (name "unconnected-(U13-PA4-Pad15)") (class "Default")
      (node (ref "U13") (pin "15") (pinfunction "PA4_15") (pintype "unspecified"))
    )
    (net (code "53") (name "unconnected-(U13-PA5-Pad16)") (class "Default")
      (node (ref "U13") (pin "16") (pinfunction "PA5_16") (pintype "unspecified"))
    )
    (net (code "54") (name "unconnected-(U13-PA8-Pad28)") (class "Default")
      (node (ref "U13") (pin "28") (pinfunction "PA8_28") (pintype "unspecified"))
    )
    (net (code "55") (name "unconnected-(U13-PA15-Pad37)") (class "Default")
      (node (ref "U13") (pin "37") (pinfunction "PA15_37") (pintype "unspecified"))
    )
    (net (code "56") (name "unconnected-(U13-PB2-Pad21)") (class "Default")
      (node (ref "U13") (pin "21") (pinfunction "PB2_21") (pintype "unspecified"))
    )
    (net (code "57") (name "unconnected-(U13-PB3-Pad42)") (class "Default")
      (node (ref "U13") (pin "42") (pinfunction "PB3_42") (pintype "unspecified"))
    )
    (net (code "58") (name "unconnected-(U13-PB4-Pad43)") (class "Default")
      (node (ref "U13") (pin "43") (pinfunction "PB4_43") (pintype "unspecified"))
    )
    (net (code "59") (name "unconnected-(U13-PB5-Pad44)") (class "Default")
      (node (ref "U13") (pin "44") (pinfunction "PB5_44") (pintype "unspecified"))
    )
    (net (code "60") (name "unconnected-(U13-PB6-Pad45)") (class "Default")
      (node (ref "U13") (pin "45") (pinfunction "PB6_45") (pintype "unspecified"))
    )
    (net (code "61") (name "unconnected-(U13-PB7-Pad46)") (class "Default")
      (node (ref "U13") (pin "46") (pinfunction "PB7_46") (pintype "unspecified"))
    )
    (net (code "62") (name "unconnected-(U13-PB8-Pad47)") (class "Default")
      (node (ref "U13") (pin "47") (pinfunction "PB8_47") (pintype "unspecified"))
    )
    (net (code "63") (name "unconnected-(U13-PB9-Pad48)") (class "Default")
      (node (ref "U13") (pin "48") (pinfunction "PB9_48") (pintype "unspecified"))
    )
    (net (code "64") (name "unconnected-(U13-PB10-Pad22)") (class "Default")
      (node (ref "U13") (pin "22") (pinfunction "PB10_22") (pintype "unspecified"))
    )
    (net (code "65") (name "unconnected-(U13-PB11-Pad23)") (class "Default")
      (node (ref "U13") (pin "23") (pinfunction "PB11_23") (pintype "unspecified"))
    )
    (net (code "66") (name "unconnected-(U13-PB12-Pad24)") (class "Default")
      (node (ref "U13") (pin "24") (pinfunction "PB12_24") (pintype "unspecified"))
    )
    (net (code "67") (name "unconnected-(U13-PB13-Pad25)") (class "Default")
      (node (ref "U13") (pin "25") (pinfunction "PB13_25") (pintype "unspecified"))
    )
    (net (code "68") (name "unconnected-(U13-PB14-Pad26)") (class "Default")
      (node (ref "U13") (pin "26") (pinfunction "PB14_26") (pintype "unspecified"))
    )
    (net (code "69") (name "unconnected-(U13-PB15-Pad27)") (class "Default")
      (node (ref "U13") (pin "27") (pinfunction "PB15_27") (pintype "unspecified"))
    )
    (net (code "70") (name "unconnected-(U13-PC6-Pad30)") (class "Default")
      (node (ref "U13") (pin "30") (pinfunction "PC6_30") (pintype "unspecified"))
    )
    (net (code "71") (name "unconnected-(U13-PC13-Pad1)") (class "Default")
      (node (ref "U13") (pin "1") (pinfunction "PC13_1") (pintype "unspecified"))
    )
    (net (code "72") (name "unconnected-(U13-PC14-OSC32_IN-Pad2)") (class "Default")
      (node (ref "U13") (pin "2") (pinfunction "PC14-OSC32_IN_2") (pintype "unspecified"))
    )
    (net (code "73") (name "unconnected-(U13-PC15-OSC32_OUT-Pad3)") (class "Default")
      (node (ref "U13") (pin "3") (pinfunction "PC15-OSC32_OUT_3") (pintype "unspecified"))
    )
    (net (code "74") (name "unconnected-(U13-PD0-Pad38)") (class "Default")
      (node (ref "U13") (pin "38") (pinfunction "PD0_38") (pintype "unspecified"))
    )
    (net (code "75") (name "unconnected-(U13-PD1-Pad39)") (class "Default")
      (node (ref "U13") (pin "39") (pinfunction "PD1_39") (pintype "unspecified"))
    )
    (net (code "76") (name "unconnected-(U13-PD2-Pad40)") (class "Default")
      (node (ref "U13") (pin "40") (pinfunction "PD2_40") (pintype "unspecified"))
    )
    (net (code "77") (name "unconnected-(U13-PD3-Pad41)") (class "Default")
      (node (ref "U13") (pin "41") (pinfunction "PD3_41") (pintype "unspecified"))
    )
    (net (code "78") (name "unconnected-(U13-PF2-NRST-Pad10)") (class "Default")
      (node (ref "U13") (pin "10") (pinfunction "PF2-NRST_10") (pintype "unspecified"))
    )
    (net (code "79") (name "unconnected-(U_USB1-CTS#-Pad9)") (class "Default")
      (node (ref "U_USB1") (pin "9") (pinfunction "CTS#_9") (pintype "unspecified"))
    )
    (net (code "80") (name "unconnected-(U_USB1-DCD#-Pad12)") (class "Default")
      (node (ref "U_USB1") (pin "12") (pinfunction "DCD#_12") (pintype "unspecified"))
    )
    (net (code "81") (name "unconnected-(U_USB1-DSR#-Pad10)") (class "Default")
      (node (ref "U_USB1") (pin "10") (pinfunction "DSR#_10") (pintype "unspecified"))
    )
    (net (code "82") (name "unconnected-(U_USB1-DTR#-Pad13)") (class "Default")
      (node (ref "U_USB1") (pin "13") (pinfunction "DTR#_13") (pintype "unspecified"))
    )
    (net (code "83") (name "unconnected-(U_USB1-NC.-Pad7)") (class "Default")
      (node (ref "U_USB1") (pin "7") (pinfunction "NC._7") (pintype "unspecified"))
    )
    (net (code "84") (name "unconnected-(U_USB1-OUT#-Pad8)") (class "Default")
      (node (ref "U_USB1") (pin "8") (pinfunction "OUT#_8") (pintype "unspecified"))
    )
    (net (code "85") (name "unconnected-(U_USB1-R232-Pad15)") (class "Default")
      (node (ref "U_USB1") (pin "15") (pinfunction "R232_15") (pintype "unspecified"))
    )
    (net (code "86") (name "unconnected-(U_USB1-RI#-Pad11)") (class "Default")
      (node (ref "U_USB1") (pin "11") (pinfunction "RI#_11") (pintype "unspecified"))
    )
    (net (code "87") (name "unconnected-(U_USB1-RTS#-Pad14)") (class "Default")
      (node (ref "U_USB1") (pin "14") (pinfunction "RTS#_14") (pintype "unspecified"))
    )
  )
)
